# STM32G473RET6_PINOUT.net
KiCad netlist of a schematic drawn in Altium Designer
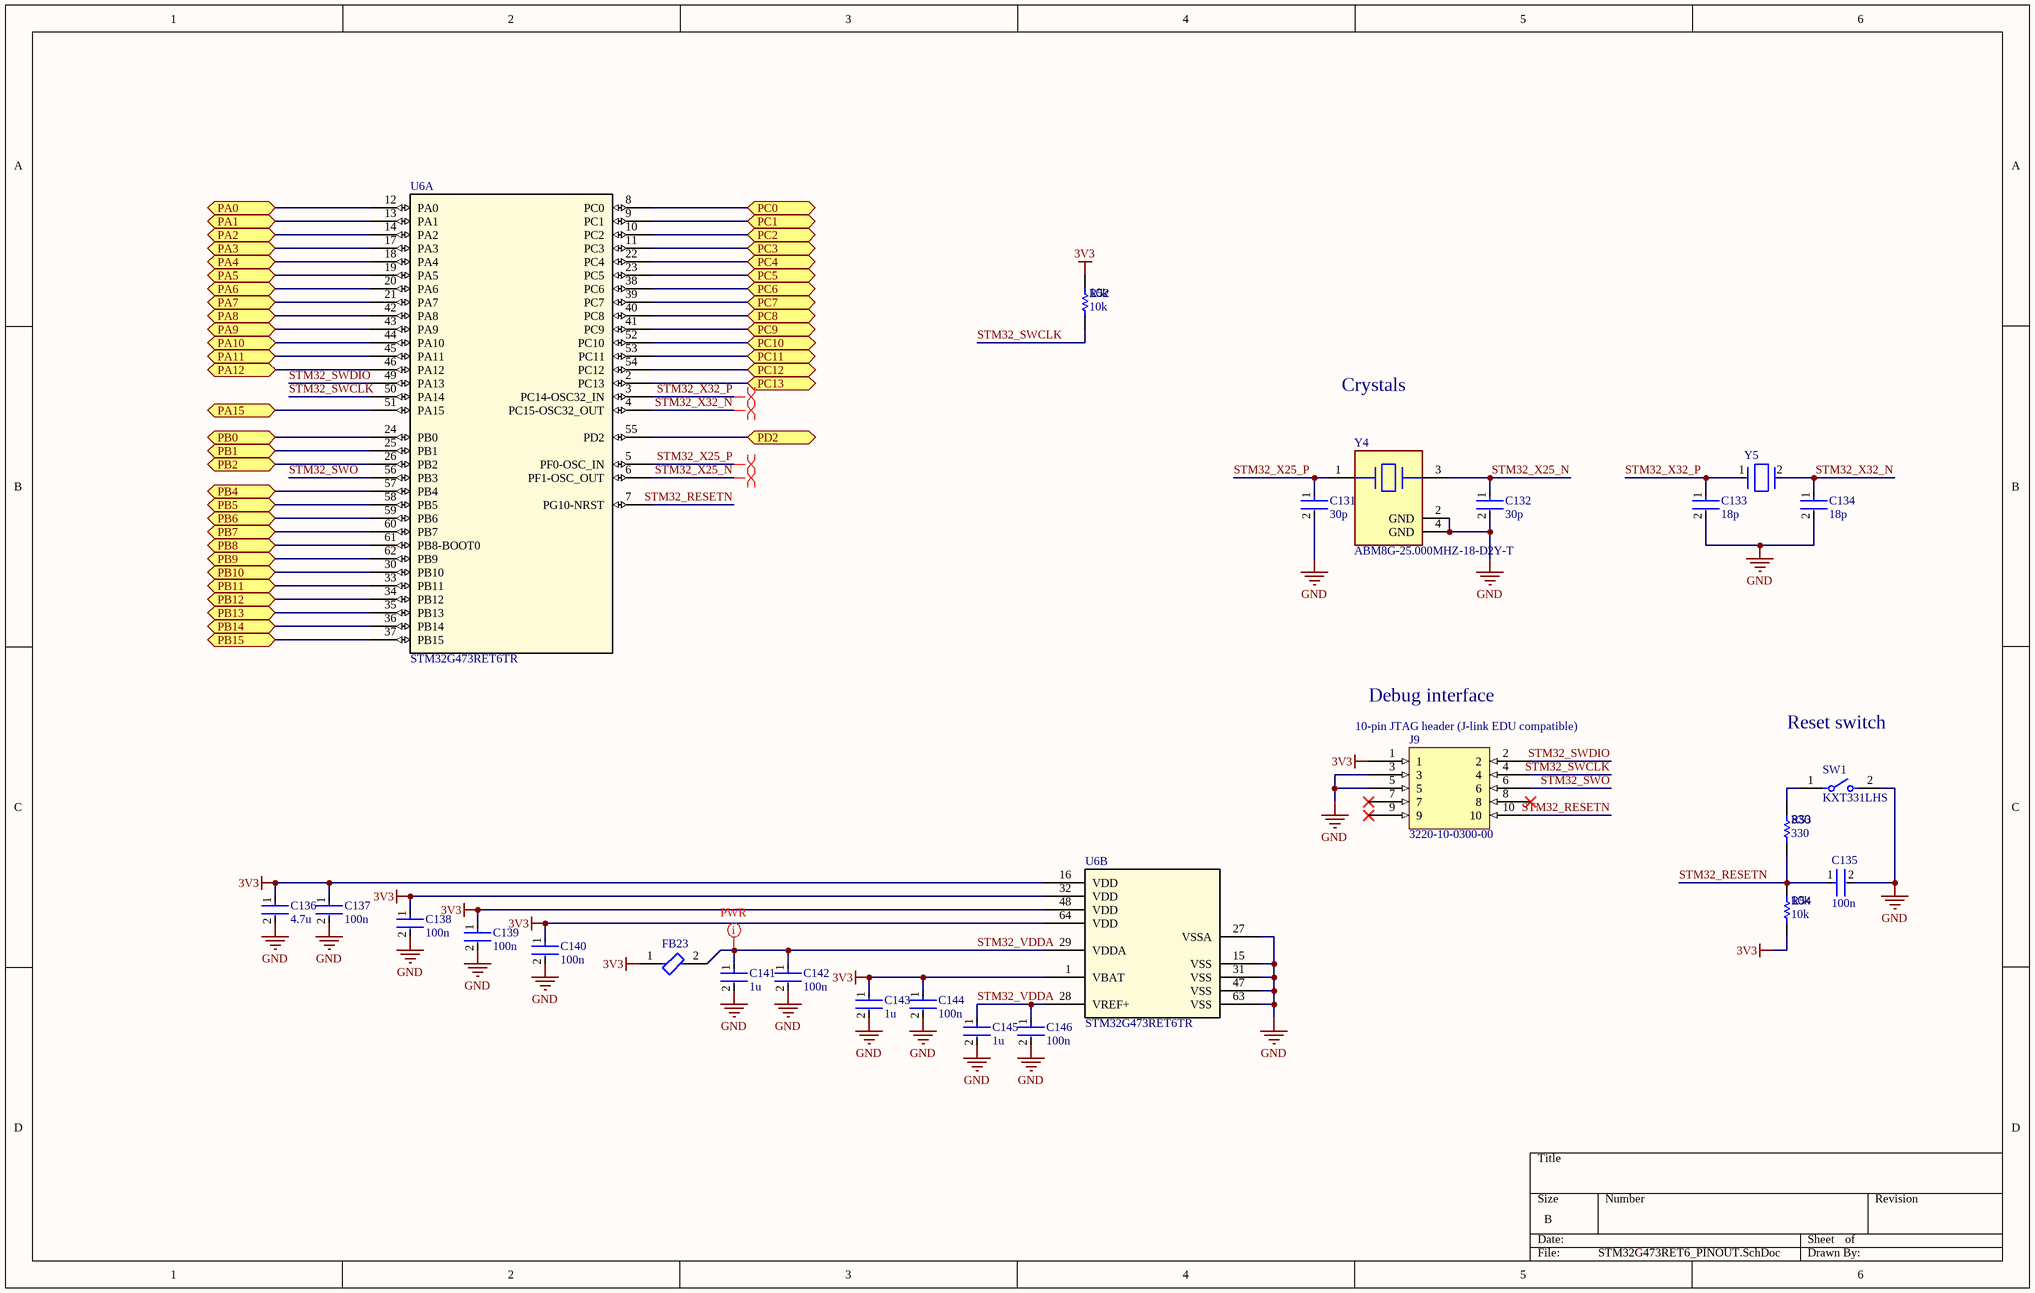
[diagram p0: STM32G473RET6_PINOUT.SchDoc]

(export (version "E")
  (design (tool "Eeschema 10.0.6"))
  (components
    (comp (ref "C131")
      (value "30p")
      (footprint "FP-0402-L_1_0_0_05-W_0_5-IPC_A")
      (description "LARGE PADS, 0402 CAP, CHANGE COMMENT TO MATCH REAL P/N")
      (libsource (lib "Space Concordia") (part "b4654b650e69147ec39a6b967a45e02"))
    )
    (comp (ref "C132")
      (value "30p")
      (footprint "FP-0402-L_1_0_0_05-W_0_5-IPC_A")
      (description "LARGE PADS, 0402 CAP, CHANGE COMMENT TO MATCH REAL P/N")
      (libsource (lib "Space Concordia") (part "b4654b650e69147ec39a6b967a45e02"))
    )
    (comp (ref "C133")
      (value "18p")
      (footprint "FP-0402-L_1_0_0_05-W_0_5-IPC_A")
      (description "LARGE PADS, 0402 CAP, CHANGE COMMENT TO MATCH REAL P/N")
      (libsource (lib "Space Concordia") (part "b4654b650e69147ec39a6b967a45e02"))
    )
    (comp (ref "C134")
      (value "18p")
      (footprint "FP-0402-L_1_0_0_05-W_0_5-IPC_A")
      (description "LARGE PADS, 0402 CAP, CHANGE COMMENT TO MATCH REAL P/N")
      (libsource (lib "Space Concordia") (part "b4654b650e69147ec39a6b967a45e02"))
    )
    (comp (ref "C135")
      (value "100n")
      (footprint "FP-0402-L_1_0_0_05-W_0_5-IPC_A")
      (description "LARGE PADS, 0402 CAP, CHANGE COMMENT TO MATCH REAL P/N")
      (libsource (lib "Space Concordia") (part "b4654b650e69147ec39a6b967a45e02"))
    )
    (comp (ref "C136")
      (value "4.7u")
      (footprint "FP-0402-L_1_0_0_05-W_0_5-IPC_A")
      (description "LARGE PADS, 0402 CAP, CHANGE COMMENT TO MATCH REAL P/N")
      (libsource (lib "Space Concordia") (part "b4654b650e69147ec39a6b967a45e02"))
    )
    (comp (ref "C137")
      (value "100n")
      (footprint "FP-0402-L_1_0_0_05-W_0_5-IPC_A")
      (description "LARGE PADS, 0402 CAP, CHANGE COMMENT TO MATCH REAL P/N")
      (libsource (lib "Space Concordia") (part "b4654b650e69147ec39a6b967a45e02"))
    )
    (comp (ref "C138")
      (value "100n")
      (footprint "FP-0402-L_1_0_0_05-W_0_5-IPC_A")
      (description "LARGE PADS, 0402 CAP, CHANGE COMMENT TO MATCH REAL P/N")
      (libsource (lib "Space Concordia") (part "b4654b650e69147ec39a6b967a45e02"))
    )
    (comp (ref "C139")
      (value "100n")
      (footprint "FP-0402-L_1_0_0_05-W_0_5-IPC_A")
      (description "LARGE PADS, 0402 CAP, CHANGE COMMENT TO MATCH REAL P/N")
      (libsource (lib "Space Concordia") (part "b4654b650e69147ec39a6b967a45e02"))
    )
    (comp (ref "C140")
      (value "100n")
      (footprint "FP-0402-L_1_0_0_05-W_0_5-IPC_A")
      (description "LARGE PADS, 0402 CAP, CHANGE COMMENT TO MATCH REAL P/N")
      (libsource (lib "Space Concordia") (part "b4654b650e69147ec39a6b967a45e02"))
    )
    (comp (ref "C141")
      (value "1u")
      (footprint "FP-0402-L_1_0_0_05-W_0_5-IPC_A")
      (description "LARGE PADS, 0402 CAP, CHANGE COMMENT TO MATCH REAL P/N")
      (libsource (lib "Space Concordia") (part "b4654b650e69147ec39a6b967a45e02"))
    )
    (comp (ref "C142")
      (value "100n")
      (footprint "FP-0402-L_1_0_0_05-W_0_5-IPC_A")
      (description "LARGE PADS, 0402 CAP, CHANGE COMMENT TO MATCH REAL P/N")
      (libsource (lib "Space Concordia") (part "b4654b650e69147ec39a6b967a45e02"))
    )
    (comp (ref "C143")
      (value "1u")
      (footprint "FP-0402-L_1_0_0_05-W_0_5-IPC_A")
      (description "LARGE PADS, 0402 CAP, CHANGE COMMENT TO MATCH REAL P/N")
      (libsource (lib "Space Concordia") (part "b4654b650e69147ec39a6b967a45e02"))
    )
    (comp (ref "C144")
      (value "100n")
      (footprint "FP-0402-L_1_0_0_05-W_0_5-IPC_A")
      (description "LARGE PADS, 0402 CAP, CHANGE COMMENT TO MATCH REAL P/N")
      (libsource (lib "Space Concordia") (part "b4654b650e69147ec39a6b967a45e02"))
    )
    (comp (ref "C145")
      (value "1u")
      (footprint "FP-0402-L_1_0_0_05-W_0_5-IPC_A")
      (description "LARGE PADS, 0402 CAP, CHANGE COMMENT TO MATCH REAL P/N")
      (libsource (lib "Space Concordia") (part "b4654b650e69147ec39a6b967a45e02"))
    )
    (comp (ref "C146")
      (value "100n")
      (footprint "FP-0402-L_1_0_0_05-W_0_5-IPC_A")
      (description "LARGE PADS, 0402 CAP, CHANGE COMMENT TO MATCH REAL P/N")
      (libsource (lib "Space Concordia") (part "b4654b650e69147ec39a6b967a45e02"))
    )
    (comp (ref "FB23")
      (value "BLM18KG331SH1D")
      (footprint "FP-BLM18-0_15-t0_8-IPC_B")
      (description "Chip Ferrite Bead, 0603, 330Ω @ 100MHz, 0.08Ω, 25%, 1.7A")
      (libsource (lib "Altium Content Vault") (part "5f30dd21d616792df468990f7003faa"))
    )
    (comp (ref "J9")
      (value "3220-10-0300-00")
      (footprint "3220-10-0300-00-Footprint-1")
      (description "CONN HEADER SMD 10POS 1.27MM")
      (libsource (lib "Space Concordia") (part "3220-10-0300-00"))
    )
    (comp (ref "R52")
      (value "10k")
      (footprint "R0603B")
      (description "Resistor")
      (fields (field (name "ALTIUM_VALUE") "10k"))
      (libsource (lib "Space Concordia") (part "Resistor"))
    )
    (comp (ref "R53")
      (value "330")
      (footprint "R0603B")
      (description "Resistor")
      (fields (field (name "ALTIUM_VALUE") "330"))
      (libsource (lib "Space Concordia") (part "Resistor"))
    )
    (comp (ref "R54")
      (value "10k")
      (footprint "R0603B")
      (description "Resistor")
      (fields (field (name "ALTIUM_VALUE") "10k"))
      (libsource (lib "Space Concordia") (part "Resistor"))
    )
    (comp (ref "SW1")
      (value "KXT331LHS")
      (footprint "FP-KXT331LHS-MFG")
      (description "SWITCH TACTILE SPST-NO 0.02A 15V")
      (libsource (lib "Altium Content Vault") (part "bb27bde45df87f1f469753f287ef5ae"))
    )
    (comp (ref "U6")
      (value "STM32G473RET6TR")
      (footprint "STM32G473RET6TR-Footprint-1")
      (description "MCU 32-Bit STM32 ARM Cortex-M4 RISC 512KB Flash 1.71V to 3.6V 64-Pin LQFP T/R")
      (libsource (lib "Space Concordia") (part "STM32G473RET6TR"))
    )
    (comp (ref "Y4")
      (value "ABM8G-25.000MHZ-18-D2Y-T")
      (footprint "FP-ABM8G-MFG")
      (description "Crystal 25MHz ±20ppm (Tol) ±30ppm (Stability) 18pF FUND 60Ω 4-Pin SMD T/R")
      (fields (field (name "TOLERANCE") "20ppm"))
      (libsource (lib "Altium Content Vault") (part "48e526d86b7f2615d98721063c72f49"))
    )
    (comp (ref "Y5")
      (value "ECS-.327-12.5-1210-TR")
      (footprint "FP-ECX-1210-MFG")
      (description "CRYSTAL 32.7680KHZ 12.5PF SMD")
      (fields
        (field (name "OCTOPART") "https://octopart.com/ecs-.327-12.5-1210-tr-ecs+international-81221340")
        (field (name "TOLERANCE") "20ppm")
      )
      (libsource (lib "Altium Content Vault") (part "99724985039315a44fd0d1401b84e49"))
    )
  )
  (nets
    (net (code "1") (name "/PA0") (class "Default")
      (node (ref "U6") (pin "12") (pinfunction "PA0_12") (pintype "bidirectional"))
    )
    (net (code "2") (name "/PA1") (class "Default")
      (node (ref "U6") (pin "13") (pinfunction "PA1_13") (pintype "bidirectional"))
    )
    (net (code "3") (name "/PA2") (class "Default")
      (node (ref "U6") (pin "14") (pinfunction "PA2_14") (pintype "bidirectional"))
    )
    (net (code "4") (name "/PA3") (class "Default")
      (node (ref "U6") (pin "17") (pinfunction "PA3_17") (pintype "bidirectional"))
    )
    (net (code "5") (name "/PA4") (class "Default")
      (node (ref "U6") (pin "18") (pinfunction "PA4_18") (pintype "bidirectional"))
    )
    (net (code "6") (name "/PA5") (class "Default")
      (node (ref "U6") (pin "19") (pinfunction "PA5_19") (pintype "bidirectional"))
    )
    (net (code "7") (name "/PA6") (class "Default")
      (node (ref "U6") (pin "20") (pinfunction "PA6_20") (pintype "bidirectional"))
    )
    (net (code "8") (name "/PA7") (class "Default")
      (node (ref "U6") (pin "21") (pinfunction "PA7_21") (pintype "bidirectional"))
    )
    (net (code "9") (name "/PA8") (class "Default")
      (node (ref "U6") (pin "42") (pinfunction "PA8_42") (pintype "bidirectional"))
    )
    (net (code "10") (name "/PA9") (class "Default")
      (node (ref "U6") (pin "43") (pinfunction "PA9_43") (pintype "bidirectional"))
    )
    (net (code "11") (name "/PA10") (class "Default")
      (node (ref "U6") (pin "44") (pinfunction "PA10_44") (pintype "bidirectional"))
    )
    (net (code "12") (name "/PA11") (class "Default")
      (node (ref "U6") (pin "45") (pinfunction "PA11_45") (pintype "bidirectional"))
    )
    (net (code "13") (name "/PA12") (class "Default")
      (node (ref "U6") (pin "46") (pinfunction "PA12_46") (pintype "bidirectional"))
    )
    (net (code "14") (name "/PA15") (class "Default")
      (node (ref "U6") (pin "51") (pinfunction "PA15_51") (pintype "bidirectional"))
    )
    (net (code "15") (name "/PB0") (class "Default")
      (node (ref "U6") (pin "24") (pinfunction "PB0_24") (pintype "bidirectional"))
    )
    (net (code "16") (name "/PB1") (class "Default")
      (node (ref "U6") (pin "25") (pinfunction "PB1_25") (pintype "bidirectional"))
    )
    (net (code "17") (name "/PB2") (class "Default")
      (node (ref "U6") (pin "26") (pinfunction "PB2_26") (pintype "bidirectional"))
    )
    (net (code "18") (name "/PB4") (class "Default")
      (node (ref "U6") (pin "57") (pinfunction "PB4_57") (pintype "bidirectional"))
    )
    (net (code "19") (name "/PB5") (class "Default")
      (node (ref "U6") (pin "58") (pinfunction "PB5_58") (pintype "bidirectional"))
    )
    (net (code "20") (name "/PB6") (class "Default")
      (node (ref "U6") (pin "59") (pinfunction "PB6_59") (pintype "bidirectional"))
    )
    (net (code "21") (name "/PB7") (class "Default")
      (node (ref "U6") (pin "60") (pinfunction "PB7_60") (pintype "bidirectional"))
    )
    (net (code "22") (name "/PB8") (class "Default")
      (node (ref "U6") (pin "61") (pinfunction "PB8-BOOT0_61") (pintype "bidirectional"))
    )
    (net (code "23") (name "/PB9") (class "Default")
      (node (ref "U6") (pin "62") (pinfunction "PB9_62") (pintype "bidirectional"))
    )
    (net (code "24") (name "/PB10") (class "Default")
      (node (ref "U6") (pin "30") (pinfunction "PB10_30") (pintype "bidirectional"))
    )
    (net (code "25") (name "/PB11") (class "Default")
      (node (ref "U6") (pin "33") (pinfunction "PB11_33") (pintype "bidirectional"))
    )
    (net (code "26") (name "/PB12") (class "Default")
      (node (ref "U6") (pin "34") (pinfunction "PB12_34") (pintype "bidirectional"))
    )
    (net (code "27") (name "/PB13") (class "Default")
      (node (ref "U6") (pin "35") (pinfunction "PB13_35") (pintype "bidirectional"))
    )
    (net (code "28") (name "/PB14") (class "Default")
      (node (ref "U6") (pin "36") (pinfunction "PB14_36") (pintype "bidirectional"))
    )
    (net (code "29") (name "/PB15") (class "Default")
      (node (ref "U6") (pin "37") (pinfunction "PB15_37") (pintype "bidirectional"))
    )
    (net (code "30") (name "/PC0") (class "Default")
      (node (ref "U6") (pin "8") (pinfunction "PC0_8") (pintype "bidirectional"))
    )
    (net (code "31") (name "/PC1") (class "Default")
      (node (ref "U6") (pin "9") (pinfunction "PC1_9") (pintype "bidirectional"))
    )
    (net (code "32") (name "/PC2") (class "Default")
      (node (ref "U6") (pin "10") (pinfunction "PC2_10") (pintype "bidirectional"))
    )
    (net (code "33") (name "/PC3") (class "Default")
      (node (ref "U6") (pin "11") (pinfunction "PC3_11") (pintype "bidirectional"))
    )
    (net (code "34") (name "/PC4") (class "Default")
      (node (ref "U6") (pin "22") (pinfunction "PC4_22") (pintype "bidirectional"))
    )
    (net (code "35") (name "/PC5") (class "Default")
      (node (ref "U6") (pin "23") (pinfunction "PC5_23") (pintype "bidirectional"))
    )
    (net (code "36") (name "/PC6") (class "Default")
      (node (ref "U6") (pin "38") (pinfunction "PC6_38") (pintype "bidirectional"))
    )
    (net (code "37") (name "/PC7") (class "Default")
      (node (ref "U6") (pin "39") (pinfunction "PC7_39") (pintype "bidirectional"))
    )
    (net (code "38") (name "/PC8") (class "Default")
      (node (ref "U6") (pin "40") (pinfunction "PC8_40") (pintype "bidirectional"))
    )
    (net (code "39") (name "/PC9") (class "Default")
      (node (ref "U6") (pin "41") (pinfunction "PC9_41") (pintype "bidirectional"))
    )
    (net (code "40") (name "/PC10") (class "Default")
      (node (ref "U6") (pin "52") (pinfunction "PC10_52") (pintype "bidirectional"))
    )
    (net (code "41") (name "/PC11") (class "Default")
      (node (ref "U6") (pin "53") (pinfunction "PC11_53") (pintype "bidirectional"))
    )
    (net (code "42") (name "/PC12") (class "Default")
      (node (ref "U6") (pin "54") (pinfunction "PC12_54") (pintype "bidirectional"))
    )
    (net (code "43") (name "/PC13") (class "Default")
      (node (ref "U6") (pin "2") (pinfunction "PC13_2") (pintype "bidirectional"))
    )
    (net (code "44") (name "/PD2") (class "Default")
      (node (ref "U6") (pin "55") (pinfunction "PD2_55") (pintype "bidirectional"))
    )
    (net (code "45") (name "/STM32_RESETN") (class "Default")
      (node (ref "C135") (pin "1") (pinfunction "1_1") (pintype "passive"))
      (node (ref "J9") (pin "10") (pinfunction "10_10") (pintype "input"))
      (node (ref "R53") (pin "1") (pinfunction "1_1") (pintype "passive"))
      (node (ref "R54") (pin "2") (pinfunction "2_2") (pintype "passive"))
      (node (ref "U6") (pin "7") (pinfunction "PG10-NRST_7") (pintype "bidirectional"))
    )
    (net (code "46") (name "/STM32_SWCLK") (class "Default")
      (node (ref "J9") (pin "4") (pinfunction "4_4") (pintype "input"))
      (node (ref "R52") (pin "1") (pinfunction "1_1") (pintype "passive"))
      (node (ref "U6") (pin "50") (pinfunction "PA14_50") (pintype "bidirectional"))
    )
    (net (code "47") (name "/STM32_SWDIO") (class "Default")
      (node (ref "J9") (pin "2") (pinfunction "2_2") (pintype "input"))
      (node (ref "U6") (pin "49") (pinfunction "PA13_49") (pintype "bidirectional"))
    )
    (net (code "48") (name "/STM32_SWO") (class "Default")
      (node (ref "J9") (pin "6") (pinfunction "6_6") (pintype "input"))
      (node (ref "U6") (pin "56") (pinfunction "PB3_56") (pintype "bidirectional"))
    )
    (net (code "49") (name "/STM32_VDDA") (class "Default")
      (node (ref "C141") (pin "1") (pinfunction "1_1") (pintype "passive"))
      (node (ref "C142") (pin "1") (pinfunction "1_1") (pintype "passive"))
      (node (ref "C145") (pin "1") (pinfunction "1_1") (pintype "passive"))
      (node (ref "C146") (pin "1") (pinfunction "1_1") (pintype "passive"))
      (node (ref "FB23") (pin "2") (pinfunction "2_2") (pintype "passive"))
      (node (ref "U6") (pin "28") (pinfunction "VREF+_28") (pintype "power_in"))
      (node (ref "U6") (pin "29") (pinfunction "VDDA_29") (pintype "power_in"))
    )
    (net (code "50") (name "/STM32_X25_N") (class "Default")
      (node (ref "C132") (pin "1") (pinfunction "1_1") (pintype "passive"))
      (node (ref "U6") (pin "6") (pinfunction "PF1-OSC_OUT_6") (pintype "bidirectional"))
      (node (ref "Y4") (pin "3") (pinfunction "3_3") (pintype "passive"))
    )
    (net (code "51") (name "/STM32_X25_P") (class "Default")
      (node (ref "C131") (pin "1") (pinfunction "1_1") (pintype "passive"))
      (node (ref "U6") (pin "5") (pinfunction "PF0-OSC_IN_5") (pintype "bidirectional"))
      (node (ref "Y4") (pin "1") (pinfunction "1_1") (pintype "passive"))
    )
    (net (code "52") (name "/STM32_X32_N") (class "Default")
      (node (ref "C134") (pin "1") (pinfunction "1_1") (pintype "passive"))
      (node (ref "U6") (pin "4") (pinfunction "PC15-OSC32_OUT_4") (pintype "bidirectional"))
      (node (ref "Y5") (pin "2") (pinfunction "Out/In_2") (pintype "passive"))
    )
    (net (code "53") (name "/STM32_X32_P") (class "Default")
      (node (ref "C133") (pin "1") (pinfunction "1_1") (pintype "passive"))
      (node (ref "U6") (pin "3") (pinfunction "PC14-OSC32_IN_3") (pintype "bidirectional"))
      (node (ref "Y5") (pin "1") (pinfunction "In/Out_1") (pintype "passive"))
    )
    (net (code "54") (name "3V3") (class "Default")
      (node (ref "C136") (pin "1") (pinfunction "1_1") (pintype "passive"))
      (node (ref "C137") (pin "1") (pinfunction "1_1") (pintype "passive"))
      (node (ref "C138") (pin "1") (pinfunction "1_1") (pintype "passive"))
      (node (ref "C139") (pin "1") (pinfunction "1_1") (pintype "passive"))
      (node (ref "C140") (pin "1") (pinfunction "1_1") (pintype "passive"))
      (node (ref "C143") (pin "1") (pinfunction "1_1") (pintype "passive"))
      (node (ref "C144") (pin "1") (pinfunction "1_1") (pintype "passive"))
      (node (ref "FB23") (pin "1") (pinfunction "1_1") (pintype "passive"))
      (node (ref "J9") (pin "1") (pinfunction "1_1") (pintype "input"))
      (node (ref "R52") (pin "2") (pinfunction "2_2") (pintype "passive"))
      (node (ref "R54") (pin "1") (pinfunction "1_1") (pintype "passive"))
      (node (ref "U6") (pin "1") (pinfunction "VBAT_1") (pintype "power_in"))
      (node (ref "U6") (pin "16") (pinfunction "VDD_16") (pintype "power_in"))
      (node (ref "U6") (pin "32") (pinfunction "VDD_32") (pintype "power_in"))
      (node (ref "U6") (pin "48") (pinfunction "VDD_48") (pintype "power_in"))
      (node (ref "U6") (pin "64") (pinfunction "VDD_64") (pintype "power_in"))
    )
    (net (code "55") (name "GND") (class "Default")
      (node (ref "C131") (pin "2") (pinfunction "2_2") (pintype "passive"))
      (node (ref "C132") (pin "2") (pinfunction "2_2") (pintype "passive"))
      (node (ref "C133") (pin "2") (pinfunction "2_2") (pintype "passive"))
      (node (ref "C134") (pin "2") (pinfunction "2_2") (pintype "passive"))
      (node (ref "C135") (pin "2") (pinfunction "2_2") (pintype "passive"))
      (node (ref "C136") (pin "2") (pinfunction "2_2") (pintype "passive"))
      (node (ref "C137") (pin "2") (pinfunction "2_2") (pintype "passive"))
      (node (ref "C138") (pin "2") (pinfunction "2_2") (pintype "passive"))
      (node (ref "C139") (pin "2") (pinfunction "2_2") (pintype "passive"))
      (node (ref "C140") (pin "2") (pinfunction "2_2") (pintype "passive"))
      (node (ref "C141") (pin "2") (pinfunction "2_2") (pintype "passive"))
      (node (ref "C142") (pin "2") (pinfunction "2_2") (pintype "passive"))
      (node (ref "C143") (pin "2") (pinfunction "2_2") (pintype "passive"))
      (node (ref "C144") (pin "2") (pinfunction "2_2") (pintype "passive"))
      (node (ref "C145") (pin "2") (pinfunction "2_2") (pintype "passive"))
      (node (ref "C146") (pin "2") (pinfunction "2_2") (pintype "passive"))
      (node (ref "J9") (pin "3") (pinfunction "3_3") (pintype "input"))
      (node (ref "J9") (pin "5") (pinfunction "5_5") (pintype "input"))
      (node (ref "SW1") (pin "2") (pinfunction "2_2") (pintype "passive"))
      (node (ref "U6") (pin "15") (pinfunction "VSS_15") (pintype "power_in"))
      (node (ref "U6") (pin "27") (pinfunction "VSSA_27") (pintype "power_in"))
      (node (ref "U6") (pin "31") (pinfunction "VSS_31") (pintype "power_in"))
      (node (ref "U6") (pin "47") (pinfunction "VSS_47") (pintype "power_in"))
      (node (ref "U6") (pin "63") (pinfunction "VSS_63") (pintype "power_in"))
      (node (ref "Y4") (pin "2") (pinfunction "GND_2") (pintype "power_in"))
      (node (ref "Y4") (pin "4") (pinfunction "GND_4") (pintype "power_in"))
    )
    (net (code "56") (name "Net-(R53-Pad2)") (class "Default")
      (node (ref "R53") (pin "2") (pinfunction "2_2") (pintype "passive"))
      (node (ref "SW1") (pin "1") (pinfunction "1_1") (pintype "passive"))
    )
    (net (code "57") (name "unconnected-(J9-Pad7)") (class "Default")
      (node (ref "J9") (pin "7") (pinfunction "7_7") (pintype "input+no_connect"))
    )
    (net (code "58") (name "unconnected-(J9-Pad8)") (class "Default")
      (node (ref "J9") (pin "8") (pinfunction "8_8") (pintype "input+no_connect"))
    )
    (net (code "59") (name "unconnected-(J9-Pad9)") (class "Default")
      (node (ref "J9") (pin "9") (pinfunction "9_9") (pintype "input+no_connect"))
    )
  )
)
